# wechselblinkerschaltung.net
KiCad netlist of a schematic drawn in EAGLE
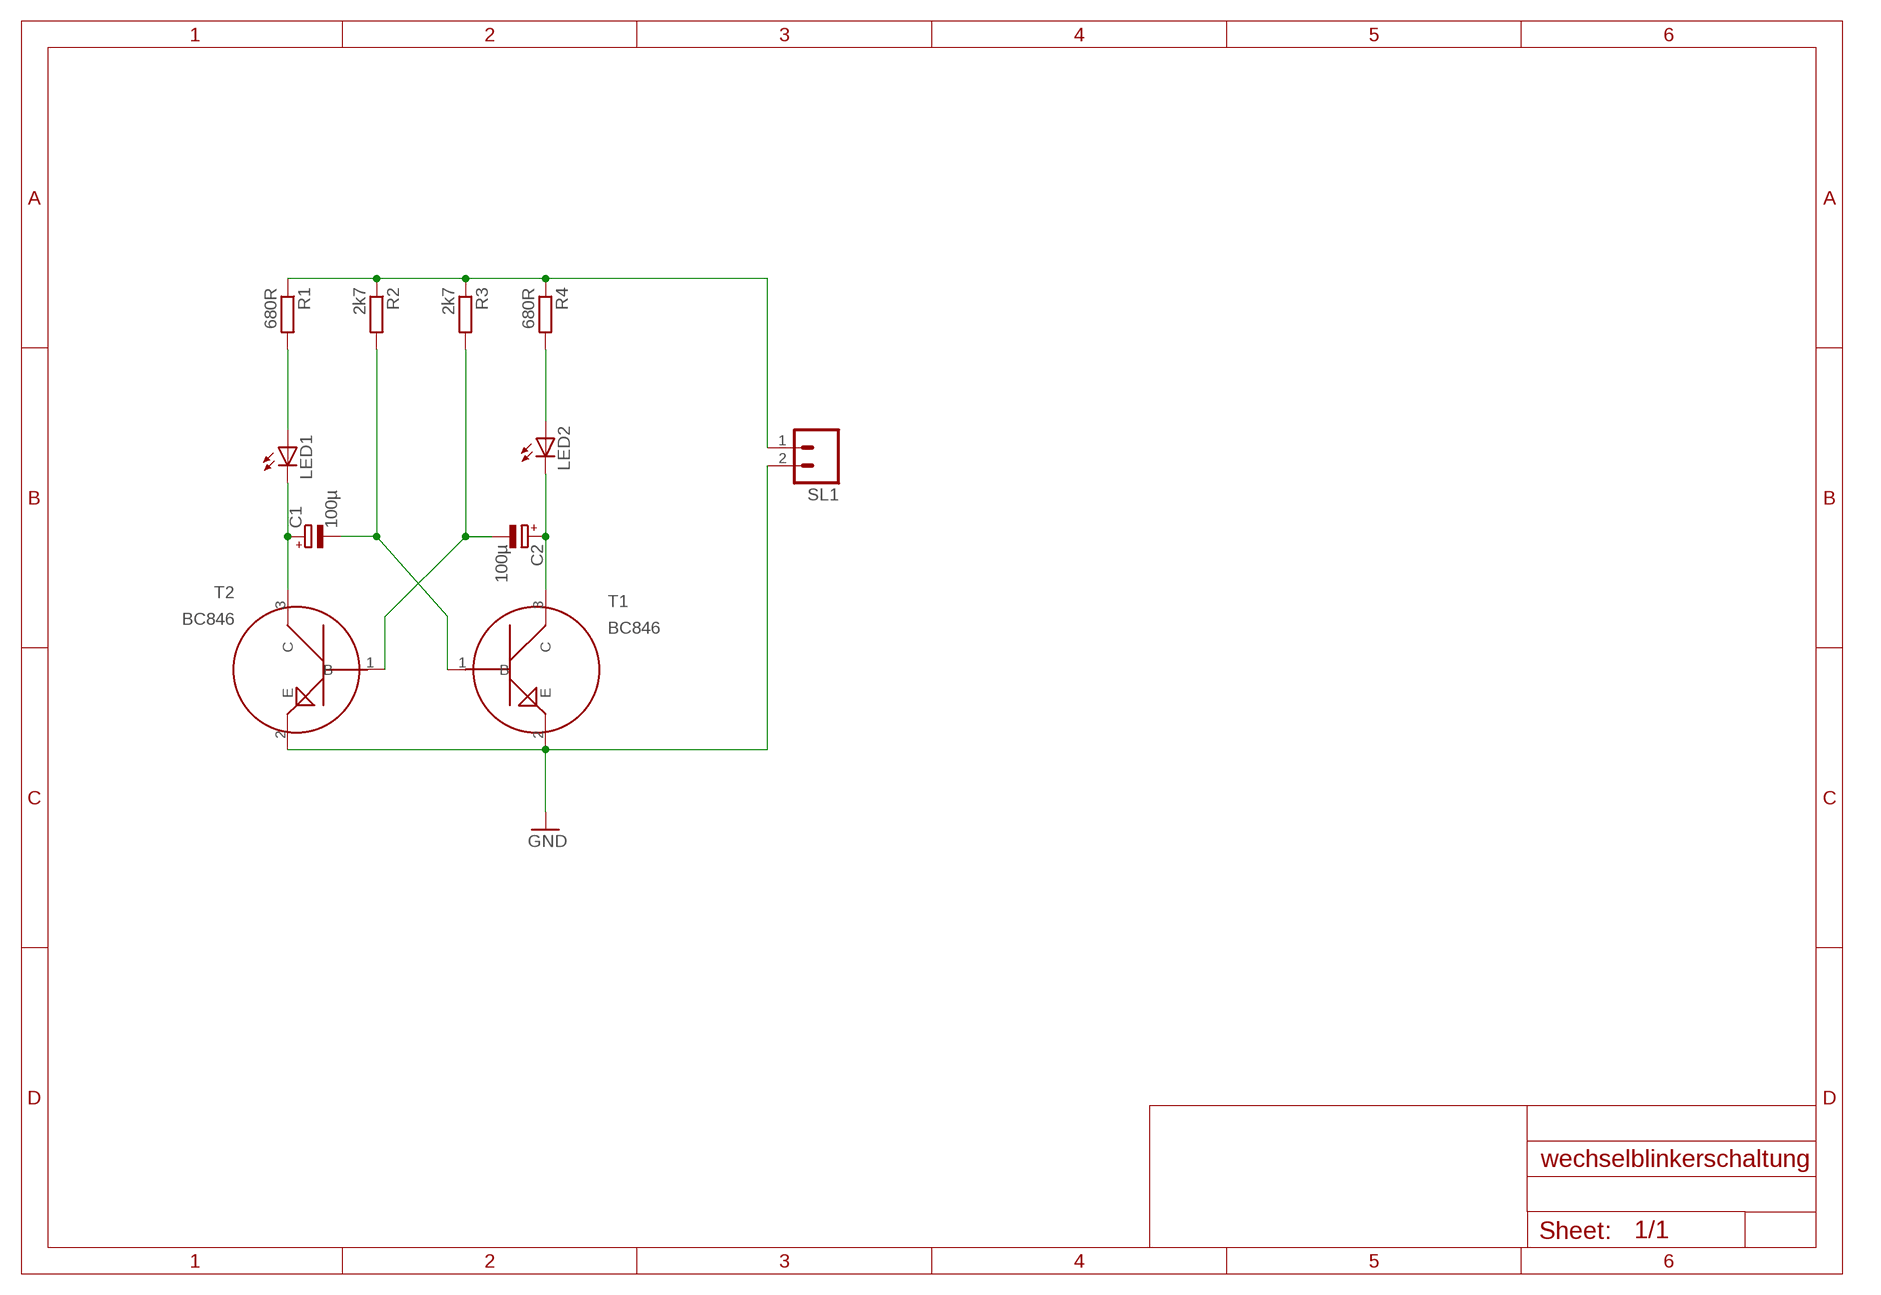
[diagram p0: schematic, sheet 1]

(export (version "E")
  (design (tool "Eeschema 10.0.6"))
  (components
    (comp (ref "C1")
      (value "100µ")
      (footprint "eagle-import:E2,5-6")
      (libsource (lib "eagle-import") (part "CPOL-EUE2.5-6"))
    )
    (comp (ref "C2")
      (value "100µ")
      (footprint "eagle-import:E2,5-6")
      (libsource (lib "eagle-import") (part "CPOL-EUE2.5-6"))
    )
    (comp (ref "LED1")
      (value "LED5MM")
      (footprint "eagle-import:LED5MM")
      (libsource (lib "eagle-import") (part "LED5MM"))
    )
    (comp (ref "LED2")
      (value "LED5MM")
      (footprint "eagle-import:LED5MM")
      (libsource (lib "eagle-import") (part "LED5MM"))
    )
    (comp (ref "R1")
      (value "680R")
      (footprint "eagle-import:R0805")
      (libsource (lib "eagle-import") (part "R-EU_R0805"))
    )
    (comp (ref "R2")
      (value "2k7")
      (footprint "eagle-import:R0805")
      (libsource (lib "eagle-import") (part "R-EU_R0805"))
    )
    (comp (ref "R3")
      (value "2k7")
      (footprint "eagle-import:R0805")
      (libsource (lib "eagle-import") (part "R-EU_R0805"))
    )
    (comp (ref "R4")
      (value "680R")
      (footprint "eagle-import:R0805")
      (libsource (lib "eagle-import") (part "R-EU_R0805"))
    )
    (comp (ref "SL1")
      (value "M02")
      (footprint "eagle-import:02P")
      (libsource (lib "eagle-import") (part "M02"))
    )
    (comp (ref "T1")
      (value "BC846")
      (footprint "eagle-import:SOT23")
      (libsource (lib "eagle-import") (part "BC846"))
    )
    (comp (ref "T2")
      (value "BC846")
      (footprint "eagle-import:SOT23")
      (libsource (lib "eagle-import") (part "BC846"))
    )
  )
  (nets
    (net (code "1") (name "GND") (class "Default")
      (node (ref "SL1") (pin "2") (pinfunction "2_2") (pintype "passive"))
      (node (ref "T1") (pin "2") (pinfunction "E_2") (pintype "bidirectional"))
      (node (ref "T2") (pin "2") (pinfunction "E_2") (pintype "bidirectional"))
    )
    (net (code "2") (name "Net-(LED1-C)") (class "Default")
      (node (ref "C1") (pin "+") (pinfunction "+_+") (pintype "passive"))
      (node (ref "LED1") (pin "K") (pinfunction "C_K") (pintype "passive"))
      (node (ref "T2") (pin "3") (pinfunction "C_3") (pintype "bidirectional"))
    )
    (net (code "3") (name "Net-(LED1-PadA)") (class "Default")
      (node (ref "LED1") (pin "A") (pinfunction "A_A") (pintype "passive"))
      (node (ref "R1") (pin "2") (pinfunction "2_2") (pintype "passive"))
    )
    (net (code "4") (name "Net-(LED2-C)") (class "Default")
      (node (ref "C2") (pin "+") (pinfunction "+_+") (pintype "passive"))
      (node (ref "LED2") (pin "K") (pinfunction "C_K") (pintype "passive"))
      (node (ref "T1") (pin "3") (pinfunction "C_3") (pintype "bidirectional"))
    )
    (net (code "5") (name "Net-(LED2-PadA)") (class "Default")
      (node (ref "LED2") (pin "A") (pinfunction "A_A") (pintype "passive"))
      (node (ref "R4") (pin "2") (pinfunction "2_2") (pintype "passive"))
    )
    (net (code "6") (name "Net-(R1-Pad1)") (class "Default")
      (node (ref "R1") (pin "1") (pinfunction "1_1") (pintype "passive"))
      (node (ref "R2") (pin "1") (pinfunction "1_1") (pintype "passive"))
      (node (ref "R3") (pin "1") (pinfunction "1_1") (pintype "passive"))
      (node (ref "R4") (pin "1") (pinfunction "1_1") (pintype "passive"))
      (node (ref "SL1") (pin "1") (pinfunction "1_1") (pintype "passive"))
    )
    (net (code "7") (name "Net-(T1-B)") (class "Default")
      (node (ref "C1") (pin "-") (pinfunction "-_-") (pintype "passive"))
      (node (ref "R2") (pin "2") (pinfunction "2_2") (pintype "passive"))
      (node (ref "T1") (pin "1") (pinfunction "B_1") (pintype "bidirectional"))
    )
    (net (code "8") (name "Net-(T2-B)") (class "Default")
      (node (ref "C2") (pin "-") (pinfunction "-_-") (pintype "passive"))
      (node (ref "R3") (pin "2") (pinfunction "2_2") (pintype "passive"))
      (node (ref "T2") (pin "1") (pinfunction "B_1") (pintype "bidirectional"))
    )
  )
)
